# Geogram_ONE.net
KiCad netlist of a schematic drawn in EAGLE
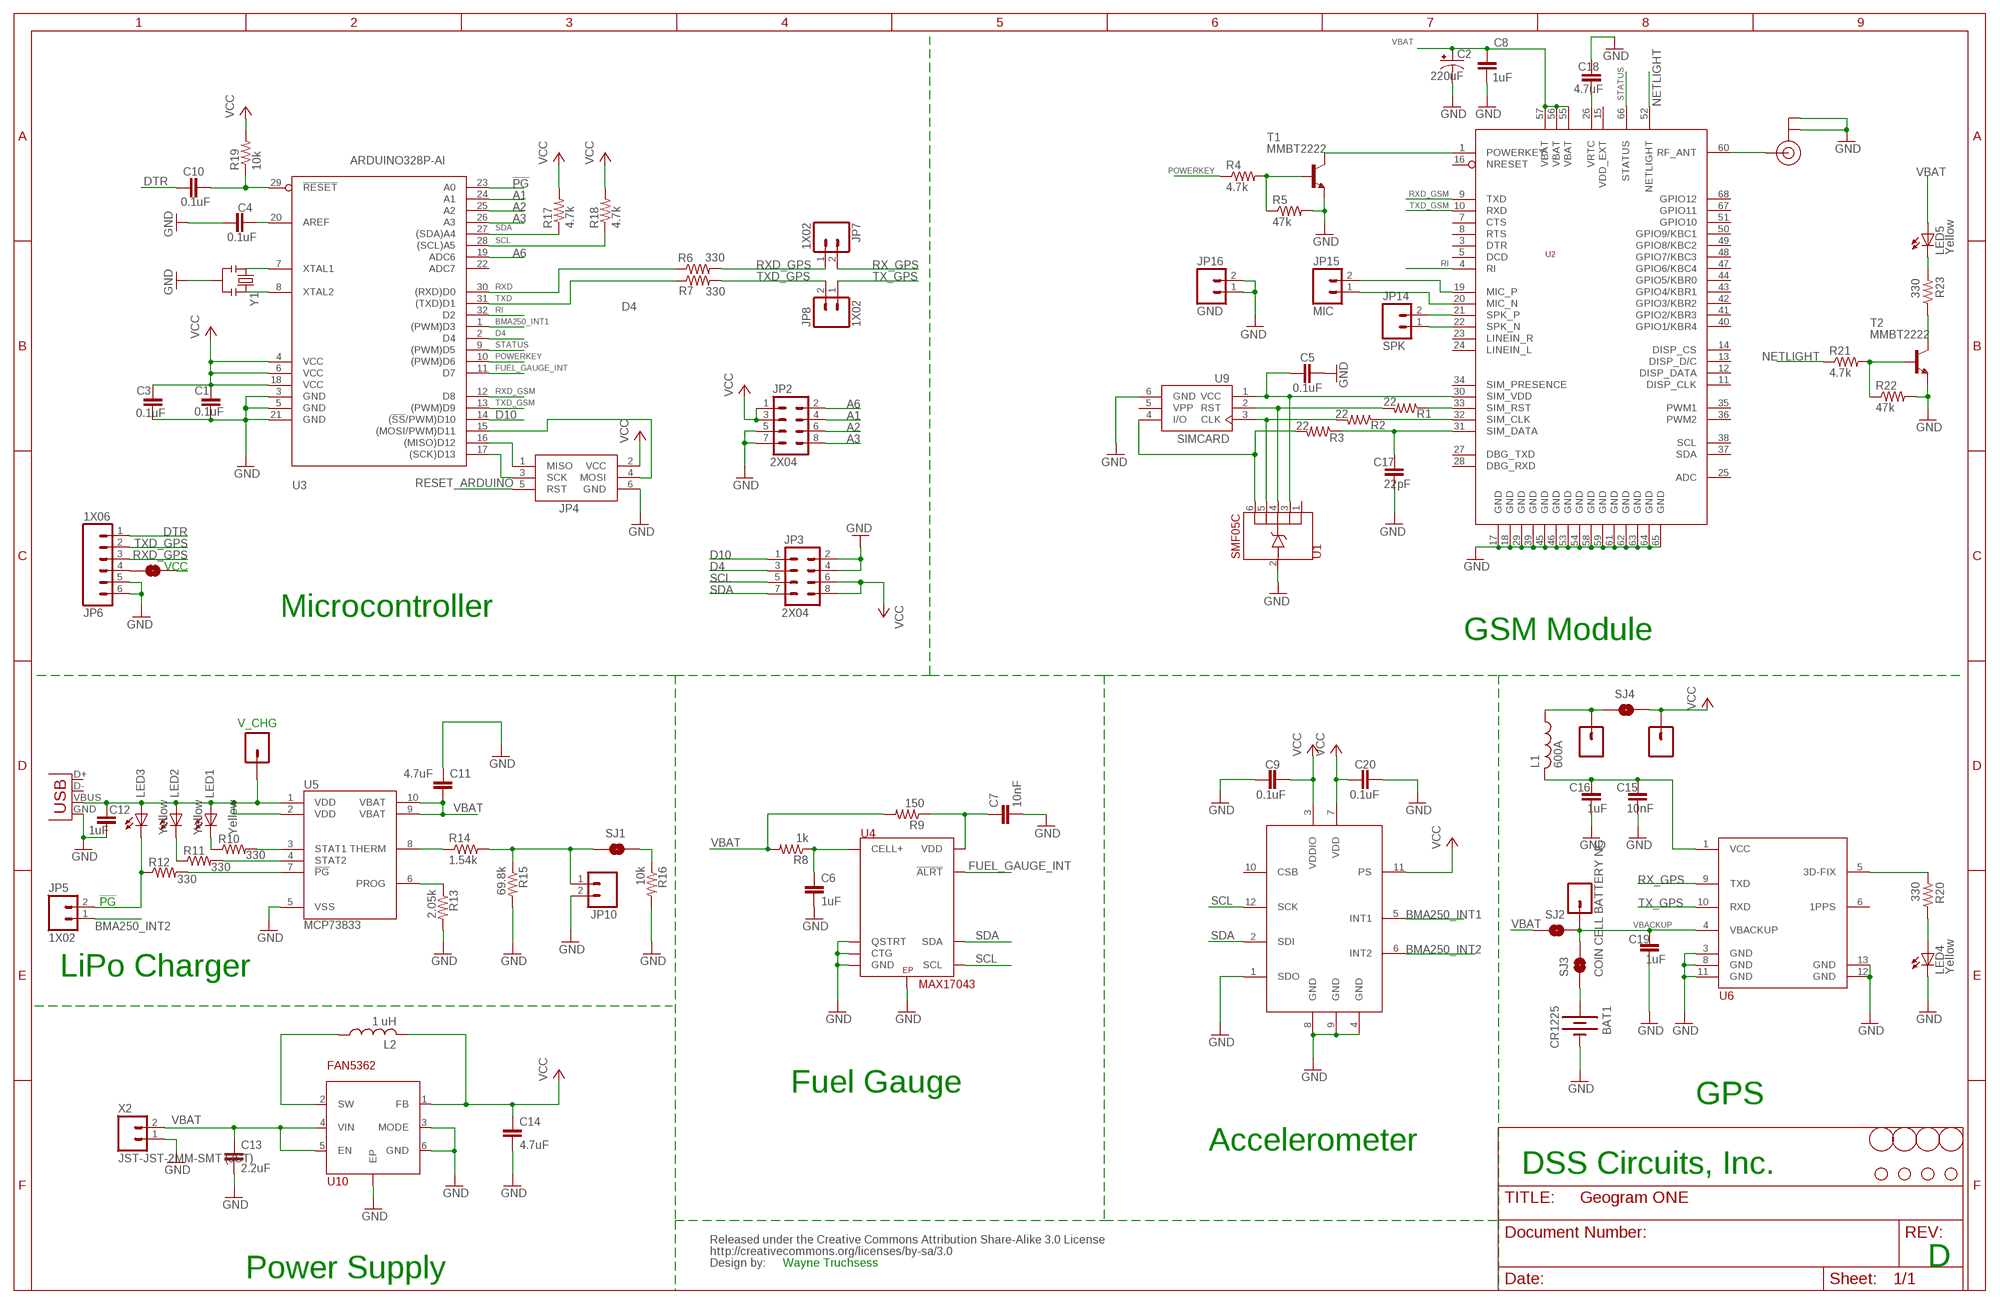
[diagram p0: schematic, sheet 1]

(export (version "E")
  (design (tool "Eeschema 10.0.6"))
  (components
    (comp (ref "BAT1")
      (value "CR1225")
      (footprint "eagle-import:BATTCON_12MM")
      (fields (field (name "MANF") "Keystone Electronics"))
      (libsource (lib "eagle-import") (part "BATTERY12MM"))
    )
    (comp (ref "C1")
      (value "0.1uF")
      (footprint "eagle-import:C0603")
      (fields (field (name "MANF") "Kemet"))
      (libsource (lib "eagle-import") (part "C-EUC0603"))
    )
    (comp (ref "C2")
      (value "220uF")
      (footprint "eagle-import:D_7343-31R")
      (fields (field (name "MANF") "Kemet"))
      (libsource (lib "eagle-import") (part "CPOL-USD/7343-31R"))
    )
    (comp (ref "C3")
      (value "0.1uF")
      (footprint "eagle-import:C0603")
      (fields (field (name "MANF") "Kemet"))
      (libsource (lib "eagle-import") (part "C-EUC0603"))
    )
    (comp (ref "C4")
      (value "0.1uF")
      (footprint "eagle-import:C0603")
      (fields (field (name "MANF") "Kemet"))
      (libsource (lib "eagle-import") (part "C-EUC0603"))
    )
    (comp (ref "C5")
      (value "0.1uF")
      (footprint "eagle-import:C0603")
      (fields (field (name "MANF") "Kemet"))
      (libsource (lib "eagle-import") (part "C-EUC0603"))
    )
    (comp (ref "C6")
      (value "1uF")
      (footprint "eagle-import:C0603")
      (fields (field (name "MANF") "TDK"))
      (libsource (lib "eagle-import") (part "C-EUC0603"))
    )
    (comp (ref "C7")
      (value "10nF")
      (footprint "eagle-import:C0603")
      (fields (field (name "MANF") "Vishay/Vitramon"))
      (libsource (lib "eagle-import") (part "C-EUC0603"))
    )
    (comp (ref "C8")
      (value "1uF")
      (footprint "eagle-import:C0603")
      (fields (field (name "MANF") "TDK"))
      (libsource (lib "eagle-import") (part "C-EUC0603"))
    )
    (comp (ref "C9")
      (value "0.1uF")
      (footprint "eagle-import:C0603")
      (fields (field (name "MANF") "Kemet"))
      (libsource (lib "eagle-import") (part "C-EUC0603"))
    )
    (comp (ref "C10")
      (value "0.1uF")
      (footprint "eagle-import:C0603")
      (fields (field (name "MANF") "Kemet"))
      (libsource (lib "eagle-import") (part "C-EUC0603"))
    )
    (comp (ref "C11")
      (value "4.7uF")
      (footprint "eagle-import:C0603")
      (fields (field (name "MANF") "Kemet"))
      (libsource (lib "eagle-import") (part "C-EUC0603"))
    )
    (comp (ref "C12")
      (value "1uF")
      (footprint "eagle-import:C0603")
      (fields (field (name "MANF") "TDK"))
      (libsource (lib "eagle-import") (part "C-EUC0603"))
    )
    (comp (ref "C13")
      (value "2.2uF")
      (footprint "eagle-import:C0603")
      (fields (field (name "MANF") "Kemet"))
      (libsource (lib "eagle-import") (part "C-EUC0603"))
    )
    (comp (ref "C14")
      (value "4.7uF")
      (footprint "eagle-import:C0603")
      (fields (field (name "MANF") "Kemet"))
      (libsource (lib "eagle-import") (part "C-EUC0603"))
    )
    (comp (ref "C15")
      (value "10nF")
      (footprint "eagle-import:C0603")
      (fields (field (name "MANF") "Vishay/Vitramon"))
      (libsource (lib "eagle-import") (part "C-EUC0603"))
    )
    (comp (ref "C16")
      (value "1uF")
      (footprint "eagle-import:C0603")
      (fields (field (name "MANF") "TDK"))
      (libsource (lib "eagle-import") (part "C-EUC0603"))
    )
    (comp (ref "C17")
      (value "22pF")
      (footprint "eagle-import:C0603")
      (fields (field (name "MANF") "Vishay/Vitramon"))
      (libsource (lib "eagle-import") (part "C-EUC0603"))
    )
    (comp (ref "C18")
      (value "4.7uF")
      (footprint "eagle-import:C0603")
      (fields (field (name "MANF") "Kemet"))
      (libsource (lib "eagle-import") (part "C-EUC0603"))
    )
    (comp (ref "C19")
      (value "1uF")
      (footprint "eagle-import:C0603")
      (fields (field (name "MANF") "TDK"))
      (libsource (lib "eagle-import") (part "C-EUC0603"))
    )
    (comp (ref "C20")
      (value "0.1uF")
      (footprint "eagle-import:C0603")
      (fields (field (name "MANF") "Kemet"))
      (libsource (lib "eagle-import") (part "C-EUC0603"))
    )
    (comp (ref "FIDUCIAL1")
      (value "FIDUCIAL")
      (footprint "eagle-import:FIDUCIAL_1MM")
      (libsource (lib "eagle-import") (part "FIDUCIAL"))
    )
    (comp (ref "FIDUCIAL2")
      (value "FIDUCIAL")
      (footprint "eagle-import:FIDUCIAL_1MM")
      (libsource (lib "eagle-import") (part "FIDUCIAL"))
    )
    (comp (ref "FIDUCIAL3")
      (value "FIDUCIAL")
      (footprint "eagle-import:FIDUCIAL_1MM")
      (libsource (lib "eagle-import") (part "FIDUCIAL"))
    )
    (comp (ref "FIDUCIAL4")
      (value "FIDUCIAL")
      (footprint "eagle-import:FIDUCIAL_1MM")
      (libsource (lib "eagle-import") (part "FIDUCIAL"))
    )
    (comp (ref "JP2")
      (value "2X04")
      (footprint "eagle-import:2X4")
      (fields (field (name "MANF") "4Ucon"))
      (libsource (lib "eagle-import") (part "M04X2"))
    )
    (comp (ref "JP3")
      (value "2X04")
      (footprint "eagle-import:2X4")
      (fields (field (name "MANF") "4Ucon"))
      (libsource (lib "eagle-import") (part "M04X2"))
    )
    (comp (ref "JP4")
      (value "AVRISP-6")
      (footprint "eagle-import:AVRISP")
      (fields (field (name "MANF") "4Ucon"))
      (libsource (lib "eagle-import") (part "AVRISP-6"))
    )
    (comp (ref "JP5")
      (value "1X02")
      (footprint "eagle-import:1X02_NO_SILK")
      (fields (field (name "MANF") "4Ucon"))
      (libsource (lib "eagle-import") (part "M021X02_NO_SILK"))
    )
    (comp (ref "JP6")
      (value "1X06")
      (footprint "eagle-import:1X06")
      (fields (field (name "MANF") "4Ucon"))
      (libsource (lib "eagle-import") (part "M06SIP"))
    )
    (comp (ref "JP7")
      (value "1X02")
      (footprint "eagle-import:1X02_NO_SILK")
      (fields (field (name "MANF") "4Ucon"))
      (libsource (lib "eagle-import") (part "M021X02_NO_SILK"))
    )
    (comp (ref "JP8")
      (value "1X02")
      (footprint "eagle-import:1X02_NO_SILK")
      (fields (field (name "MANF") "4Ucon"))
      (libsource (lib "eagle-import") (part "M021X02_NO_SILK"))
    )
    (comp (ref "JP9")
      (value "V_CHG")
      (footprint "eagle-import:1X01")
      (libsource (lib "eagle-import") (part "M01PTH"))
    )
    (comp (ref "JP10")
      (value "EXT THERMISTER")
      (footprint "eagle-import:1X02_NO_SILK")
      (libsource (lib "eagle-import") (part "M021X02_NO_SILK"))
    )
    (comp (ref "JP11")
      (value "EXT_BAT")
      (footprint "eagle-import:1X01")
      (libsource (lib "eagle-import") (part "M01PTH"))
    )
    (comp (ref "JP12")
      (value "EXT GPS POWER JPR")
      (footprint "eagle-import:1X01")
      (libsource (lib "eagle-import") (part "M01PTH"))
    )
    (comp (ref "JP13")
      (value "EXT GPS POWER JPR")
      (footprint "eagle-import:1X01")
      (libsource (lib "eagle-import") (part "M01PTH"))
    )
    (comp (ref "JP14")
      (value "SPK")
      (footprint "eagle-import:1X02_NO_SILK")
      (libsource (lib "eagle-import") (part "M021X02_NO_SILK"))
    )
    (comp (ref "JP15")
      (value "MIC")
      (footprint "eagle-import:1X02_NO_SILK")
      (libsource (lib "eagle-import") (part "M021X02_NO_SILK"))
    )
    (comp (ref "JP16")
      (value "GND")
      (footprint "eagle-import:1X02_NO_SILK")
      (libsource (lib "eagle-import") (part "M021X02_NO_SILK"))
    )
    (comp (ref "L1")
      (value "600A")
      (footprint "eagle-import:L2012C")
      (fields (field (name "MANF") "TDK"))
      (libsource (lib "eagle-import") (part "L-USL2012C"))
    )
    (comp (ref "L2")
      (value "1 uH")
      (footprint "eagle-import:L2012C")
      (fields (field (name "MANF") "Murata"))
      (libsource (lib "eagle-import") (part "L-USL2012C"))
    )
    (comp (ref "LED1")
      (value "Yellow")
      (footprint "eagle-import:CHIP-LED0603")
      (fields (field (name "MANF") "OSRAM Opto Semiconductors"))
      (libsource (lib "eagle-import") (part "LEDCHIP-LED0603"))
    )
    (comp (ref "LED2")
      (value "Yellow")
      (footprint "eagle-import:CHIP-LED0603")
      (fields (field (name "MANF") "OSRAM Opto Semiconductors"))
      (libsource (lib "eagle-import") (part "LEDCHIP-LED0603"))
    )
    (comp (ref "LED3")
      (value "Yellow")
      (footprint "eagle-import:CHIP-LED0603")
      (fields (field (name "MANF") "OSRAM Opto Semiconductors"))
      (libsource (lib "eagle-import") (part "LEDCHIP-LED0603"))
    )
    (comp (ref "LED4")
      (value "Yellow")
      (footprint "eagle-import:CHIP-LED0603")
      (fields (field (name "MANF") "OSRAM Opto Semiconductors"))
      (libsource (lib "eagle-import") (part "LEDCHIP-LED0603"))
    )
    (comp (ref "LED5")
      (value "Yellow")
      (footprint "eagle-import:CHIP-LED0603")
      (fields (field (name "MANF") "OSRAM Opto Semiconductors"))
      (libsource (lib "eagle-import") (part "LEDCHIP-LED0603"))
    )
    (comp (ref "LICENSE")
      (value "CREATIVE_COMMONS")
      (footprint "eagle-import:CREATIVE_COMMONS")
      (libsource (lib "eagle-import") (part "CREATIVE_COMMONS"))
    )
    (comp (ref "R1")
      (value "22")
      (footprint "eagle-import:R0603")
      (fields (field (name "MANF") "Panasonic Electronic Components"))
      (libsource (lib "eagle-import") (part "R-US_R0603"))
    )
    (comp (ref "R2")
      (value "22")
      (footprint "eagle-import:R0603")
      (fields (field (name "MANF") "Panasonic Electronic Components"))
      (libsource (lib "eagle-import") (part "R-US_R0603"))
    )
    (comp (ref "R3")
      (value "22")
      (footprint "eagle-import:R0603")
      (fields (field (name "MANF") "Panasonic Electronic Components"))
      (libsource (lib "eagle-import") (part "R-US_R0603"))
    )
    (comp (ref "R4")
      (value "4.7k")
      (footprint "eagle-import:R0603")
      (fields (field (name "MANF") "Panasonic Electronic Components"))
      (libsource (lib "eagle-import") (part "R-US_R0603"))
    )
    (comp (ref "R5")
      (value "47k")
      (footprint "eagle-import:R0603")
      (fields (field (name "MANF") "Panasonic Electronic Components"))
      (libsource (lib "eagle-import") (part "R-US_R0603"))
    )
    (comp (ref "R6")
      (value "330")
      (footprint "eagle-import:R0603")
      (fields (field (name "MANF") "Panasonic Electronic Components"))
      (libsource (lib "eagle-import") (part "R-US_R0603"))
    )
    (comp (ref "R7")
      (value "330")
      (footprint "eagle-import:R0603")
      (fields (field (name "MANF") "Panasonic Electronic Components"))
      (libsource (lib "eagle-import") (part "R-US_R0603"))
    )
    (comp (ref "R8")
      (value "1k")
      (footprint "eagle-import:R0603")
      (fields (field (name "MANF") "Panasonic Electronic Components"))
      (libsource (lib "eagle-import") (part "R-US_R0603"))
    )
    (comp (ref "R9")
      (value "150")
      (footprint "eagle-import:R0603")
      (fields (field (name "MANF") "Panasonic Electronic Components"))
      (libsource (lib "eagle-import") (part "R-US_R0603"))
    )
    (comp (ref "R10")
      (value "330")
      (footprint "eagle-import:R0603")
      (fields (field (name "MANF") "Panasonic Electronic Components"))
      (libsource (lib "eagle-import") (part "R-US_R0603"))
    )
    (comp (ref "R11")
      (value "330")
      (footprint "eagle-import:R0603")
      (fields (field (name "MANF") "Panasonic Electronic Components"))
      (libsource (lib "eagle-import") (part "R-US_R0603"))
    )
    (comp (ref "R12")
      (value "330")
      (footprint "eagle-import:R0603")
      (fields (field (name "MANF") "Panasonic Electronic Components"))
      (libsource (lib "eagle-import") (part "R-US_R0603"))
    )
    (comp (ref "R13")
      (value "2.05k")
      (footprint "eagle-import:R0603")
      (fields (field (name "MANF") "Panasonic Electronic Components"))
      (libsource (lib "eagle-import") (part "R-US_R0603"))
    )
    (comp (ref "R14")
      (value "1.54k")
      (footprint "eagle-import:R0603")
      (fields (field (name "MANF") "Vishay/Dale"))
      (libsource (lib "eagle-import") (part "R-US_R0603"))
    )
    (comp (ref "R15")
      (value "69.8k")
      (footprint "eagle-import:R0603")
      (fields (field (name "MANF") "Panasonic Electronic Components"))
      (libsource (lib "eagle-import") (part "R-US_R0603"))
    )
    (comp (ref "R16")
      (value "10k")
      (footprint "eagle-import:R0603")
      (fields (field (name "MANF") "Panasonic Electronic Components"))
      (libsource (lib "eagle-import") (part "R-US_R0603"))
    )
    (comp (ref "R17")
      (value "4.7k")
      (footprint "eagle-import:R0603")
      (fields (field (name "MANF") "Panasonic Electronic Components"))
      (libsource (lib "eagle-import") (part "R-US_R0603"))
    )
    (comp (ref "R18")
      (value "4.7k")
      (footprint "eagle-import:R0603")
      (fields (field (name "MANF") "Panasonic Electronic Components"))
      (libsource (lib "eagle-import") (part "R-US_R0603"))
    )
    (comp (ref "R19")
      (value "10k")
      (footprint "eagle-import:R0603")
      (fields (field (name "MANF") "Panasonic Electronic Components"))
      (libsource (lib "eagle-import") (part "R-US_R0603"))
    )
    (comp (ref "R20")
      (value "330")
      (footprint "eagle-import:R0603")
      (fields (field (name "MANF") "Panasonic Electronic Components"))
      (libsource (lib "eagle-import") (part "R-US_R0603"))
    )
    (comp (ref "R21")
      (value "4.7k")
      (footprint "eagle-import:R0603")
      (fields (field (name "MANF") "Panasonic Electronic Components"))
      (libsource (lib "eagle-import") (part "R-US_R0603"))
    )
    (comp (ref "R22")
      (value "47k")
      (footprint "eagle-import:R0603")
      (fields (field (name "MANF") "Panasonic Electronic Components"))
      (libsource (lib "eagle-import") (part "R-US_R0603"))
    )
    (comp (ref "R23")
      (value "330")
      (footprint "eagle-import:R0603")
      (fields (field (name "MANF") "Panasonic Electronic Components"))
      (libsource (lib "eagle-import") (part "R-US_R0603"))
    )
    (comp (ref "SJ1")
      (value "EXT THERMISTER NC")
      (footprint "eagle-import:SJ_2S-TRACE")
      (libsource (lib "eagle-import") (part "SOLDERJUMPERTRACE"))
    )
    (comp (ref "SJ2")
      (value "LIPO BATTERY NO")
      (footprint "eagle-import:SJ_2S-NO")
      (libsource (lib "eagle-import") (part "SOLDERJUMPERNO"))
    )
    (comp (ref "SJ3")
      (value "COIN CELL BATTERY NC")
      (footprint "eagle-import:SJ_2S-TRACE")
      (libsource (lib "eagle-import") (part "SOLDERJUMPERTRACE"))
    )
    (comp (ref "SJ4")
      (value "EXT GPS POWER NC")
      (footprint "eagle-import:SJ_2S-TRACE")
      (libsource (lib "eagle-import") (part "SOLDERJUMPERTRACE"))
    )
    (comp (ref "SJ5")
      (value "EXT VCC NO")
      (footprint "eagle-import:SJ_2S-NO")
      (libsource (lib "eagle-import") (part "SOLDERJUMPERNO"))
    )
    (comp (ref "STANDOFF1")
      (value "STAND-OFF")
      (footprint "eagle-import:STAND-OFF")
      (libsource (lib "eagle-import") (part "STAND-OFF"))
    )
    (comp (ref "STANDOFF2")
      (value "STAND-OFF")
      (footprint "eagle-import:STAND-OFF")
      (libsource (lib "eagle-import") (part "STAND-OFF"))
    )
    (comp (ref "STANDOFF3")
      (value "STAND-OFF")
      (footprint "eagle-import:STAND-OFF")
      (libsource (lib "eagle-import") (part "STAND-OFF"))
    )
    (comp (ref "STANDOFF4")
      (value "STAND-OFF")
      (footprint "eagle-import:STAND-OFF")
      (libsource (lib "eagle-import") (part "STAND-OFF"))
    )
    (comp (ref "T1")
      (value "MMBT2222")
      (footprint "eagle-import:SOT23-BEC")
      (fields (field (name "MANF") "Fairchild Semiconductor"))
      (libsource (lib "eagle-import") (part "-NPN-SOT23-BECMMBT2222ALT1"))
    )
    (comp (ref "T2")
      (value "MMBT2222")
      (footprint "eagle-import:SOT23-BEC")
      (fields (field (name "MANF") "Fairchild Semiconductor"))
      (libsource (lib "eagle-import") (part "-NPN-SOT23-BECMMBT2222ALT1"))
    )
    (comp (ref "U1")
      (value "SMF05C")
      (footprint "eagle-import:SC70-6L")
      (fields (field (name "MANF") "Semtech"))
      (libsource (lib "eagle-import") (part "SMF05C"))
    )
    (comp (ref "U2")
      (value "SIM900")
      (footprint "eagle-import:SIM900")
      (fields (field (name "MANF") "Simcom"))
      (libsource (lib "eagle-import") (part "SIM900"))
    )
    (comp (ref "U3")
      (value "ARDUINO328P-AI")
      (footprint "eagle-import:TQFP32-08")
      (fields (field (name "MANF") "Atmel"))
      (libsource (lib "eagle-import") (part "ARDUINO328P-AI"))
    )
    (comp (ref "U4")
      (value "MAX17043")
      (footprint "eagle-import:TDFN8")
      (fields (field (name "MANF") "Maxim Integrated Products"))
      (libsource (lib "eagle-import") (part "MAX17043"))
    )
    (comp (ref "U5")
      (value "MCP73833")
      (footprint "eagle-import:MSOP-10")
      (fields (field (name "MANF") "Microchip Technology"))
      (libsource (lib "eagle-import") (part "MCP73833"))
    )
    (comp (ref "U6")
      (value "PA6C")
      (footprint "eagle-import:PA6C")
      (fields (field (name "MANF") "GlobalTop Inc."))
      (libsource (lib "eagle-import") (part "PA6C"))
    )
    (comp (ref "U7")
      (value "BMA250")
      (footprint "eagle-import:12LGA_VGG3-D")
      (fields (field (name "MANF") "Bosch Sensortec"))
      (libsource (lib "eagle-import") (part "BMA250"))
    )
    (comp (ref "U8")
      (value "U.FL")
      (footprint "eagle-import:U.FL")
      (fields (field (name "MANF") "Taoglas"))
      (libsource (lib "eagle-import") (part "U.FL"))
    )
    (comp (ref "U9")
      (value "SIMCARD")
      (footprint "eagle-import:SIMCARD")
      (fields (field (name "MANF") "FCI"))
      (libsource (lib "eagle-import") (part "SIMCARD"))
    )
    (comp (ref "U10")
      (value "FAN5362")
      (footprint "eagle-import:UMLP")
      (fields (field (name "MANF") "Fairchild Semiconductor"))
      (libsource (lib "eagle-import") (part "FAN5362"))
    )
    (comp (ref "X1")
      (value "USBSMD")
      (footprint "eagle-import:USB-MINIB")
      (fields (field (name "MANF") "On Shore Technology Inc"))
      (libsource (lib "eagle-import") (part "USBSMD"))
    )
    (comp (ref "X2")
      (value "JST-JST-2MM-SMT (JST)")
      (footprint "eagle-import:JST")
      (fields (field (name "MANF") "4Ucon"))
      (libsource (lib "eagle-import") (part "JST-JST-2MM-SMT"))
    )
    (comp (ref "Y1")
      (value "8 MHz")
      (footprint "eagle-import:RESONATOR-SMD")
      (fields (field (name "MANF") "Murata"))
      (libsource (lib "eagle-import") (part "RESONATORSMD"))
    )
  )
  (nets
    (net (code "1") (name "/A1") (class "Default")
      (node (ref "JP2") (pin "4") (pinfunction "4_4") (pintype "passive"))
      (node (ref "U3") (pin "24") (pinfunction "A1_24") (pintype "bidirectional"))
    )
    (net (code "2") (name "/A2") (class "Default")
      (node (ref "JP2") (pin "6") (pinfunction "6_6") (pintype "passive"))
      (node (ref "U3") (pin "25") (pinfunction "A2_25") (pintype "bidirectional"))
    )
    (net (code "3") (name "/A3") (class "Default")
      (node (ref "JP2") (pin "8") (pinfunction "8_8") (pintype "passive"))
      (node (ref "U3") (pin "26") (pinfunction "A3_26") (pintype "bidirectional"))
    )
    (net (code "4") (name "/A6") (class "Default")
      (node (ref "JP2") (pin "2") (pinfunction "2_2") (pintype "passive"))
      (node (ref "U3") (pin "19") (pinfunction "ADC6_19") (pintype "bidirectional"))
    )
    (net (code "5") (name "/BMA250_INT1") (class "Default")
      (node (ref "U3") (pin "1") (pinfunction "(PWM)D3_1") (pintype "bidirectional"))
      (node (ref "U7") (pin "5") (pinfunction "INT1_5") (pintype "bidirectional"))
    )
    (net (code "6") (name "/BMA250_INT2") (class "Default")
      (node (ref "JP5") (pin "1") (pinfunction "1_1") (pintype "passive"))
      (node (ref "U7") (pin "6") (pinfunction "INT2_6") (pintype "bidirectional"))
    )
    (net (code "7") (name "/D4") (class "Default")
      (node (ref "JP3") (pin "3") (pinfunction "3_3") (pintype "passive"))
      (node (ref "U3") (pin "2") (pinfunction "D4_2") (pintype "bidirectional"))
    )
    (net (code "8") (name "/D10") (class "Default")
      (node (ref "JP3") (pin "1") (pinfunction "1_1") (pintype "passive"))
      (node (ref "U3") (pin "14") (pinfunction "(~{SS}/PWM)D10_14") (pintype "bidirectional"))
    )
    (net (code "9") (name "/DTR") (class "Default")
      (node (ref "C10") (pin "1") (pinfunction "1_1") (pintype "passive"))
      (node (ref "JP6") (pin "1") (pinfunction "1_1") (pintype "passive"))
    )
    (net (code "10") (name "/FUEL_GAUGE_INT") (class "Default")
      (node (ref "U3") (pin "11") (pinfunction "D7_11") (pintype "bidirectional"))
      (node (ref "U4") (pin "!ALRT") (pinfunction "~{ALRT}_!ALRT") (pintype "bidirectional"))
    )
    (net (code "11") (name "/N$24") (class "Default")
      (node (ref "JP12") (pin "1") (pinfunction "1_1") (pintype "passive"))
      (node (ref "L1") (pin "1") (pinfunction "1_1") (pintype "passive"))
      (node (ref "SJ4") (pin "1") (pinfunction "1_1") (pintype "passive"))
      (node (ref "SJ5") (pin "1") (pinfunction "1_1") (pintype "passive"))
    )
    (net (code "12") (name "/NETLIGHT") (class "Default")
      (node (ref "R21") (pin "1") (pinfunction "1_1") (pintype "passive"))
      (node (ref "U2") (pin "52") (pinfunction "NETLIGHT_52") (pintype "bidirectional"))
    )
    (net (code "13") (name "/POWERKEY") (class "Default")
      (node (ref "R4") (pin "1") (pinfunction "1_1") (pintype "passive"))
      (node (ref "U3") (pin "10") (pinfunction "(PWM)D6_10") (pintype "bidirectional"))
    )
    (net (code "14") (name "/RESET_ARDUINO") (class "Default")
      (node (ref "C10") (pin "2") (pinfunction "2_2") (pintype "passive"))
      (node (ref "JP4") (pin "5") (pinfunction "RST_5") (pintype "output"))
      (node (ref "R19") (pin "1") (pinfunction "1_1") (pintype "passive"))
      (node (ref "U3") (pin "29") (pinfunction "~{RESET}_29") (pintype "input"))
    )
    (net (code "15") (name "/RI") (class "Default")
      (node (ref "U2") (pin "4") (pinfunction "RI_4") (pintype "bidirectional"))
      (node (ref "U3") (pin "32") (pinfunction "D2_32") (pintype "bidirectional"))
    )
    (net (code "16") (name "/RXD") (class "Default")
      (node (ref "R6") (pin "1") (pinfunction "1_1") (pintype "passive"))
      (node (ref "U3") (pin "30") (pinfunction "(RXD)D0_30") (pintype "bidirectional"))
    )
    (net (code "17") (name "/RXD_GPS") (class "Default")
      (node (ref "JP6") (pin "3") (pinfunction "3_3") (pintype "passive"))
      (node (ref "JP7") (pin "1") (pinfunction "1_1") (pintype "passive"))
      (node (ref "R6") (pin "2") (pinfunction "2_2") (pintype "passive"))
    )
    (net (code "18") (name "/RXD_GSM") (class "Default")
      (node (ref "U2") (pin "9") (pinfunction "TXD_9") (pintype "bidirectional"))
      (node (ref "U3") (pin "12") (pinfunction "D8_12") (pintype "bidirectional"))
    )
    (net (code "19") (name "/RX_GPS") (class "Default")
      (node (ref "JP7") (pin "2") (pinfunction "2_2") (pintype "passive"))
      (node (ref "U6") (pin "9") (pinfunction "TXD_9") (pintype "output"))
    )
    (net (code "20") (name "/SCL") (class "Default")
      (node (ref "JP3") (pin "5") (pinfunction "5_5") (pintype "passive"))
      (node (ref "R18") (pin "1") (pinfunction "1_1") (pintype "passive"))
      (node (ref "U3") (pin "28") (pinfunction "(SCL)A5_28") (pintype "bidirectional"))
      (node (ref "U4") (pin "SCL") (pinfunction "SCL_SCL") (pintype "bidirectional"))
      (node (ref "U7") (pin "12") (pinfunction "SCK_12") (pintype "bidirectional"))
    )
    (net (code "21") (name "/SDA") (class "Default")
      (node (ref "JP3") (pin "7") (pinfunction "7_7") (pintype "passive"))
      (node (ref "R17") (pin "1") (pinfunction "1_1") (pintype "passive"))
      (node (ref "U3") (pin "27") (pinfunction "(SDA)A4_27") (pintype "bidirectional"))
      (node (ref "U4") (pin "SDA") (pinfunction "SDA_SDA") (pintype "bidirectional"))
      (node (ref "U7") (pin "2") (pinfunction "SDI_2") (pintype "bidirectional"))
    )
    (net (code "22") (name "/STATUS") (class "Default")
      (node (ref "U2") (pin "66") (pinfunction "STATUS_66") (pintype "bidirectional"))
      (node (ref "U3") (pin "9") (pinfunction "(PWM)D5_9") (pintype "bidirectional"))
    )
    (net (code "23") (name "/TXD") (class "Default")
      (node (ref "R7") (pin "1") (pinfunction "1_1") (pintype "passive"))
      (node (ref "U3") (pin "31") (pinfunction "(TXD)D1_31") (pintype "bidirectional"))
    )
    (net (code "24") (name "/TXD_GPS") (class "Default")
      (node (ref "JP6") (pin "2") (pinfunction "2_2") (pintype "passive"))
      (node (ref "JP8") (pin "2") (pinfunction "2_2") (pintype "passive"))
      (node (ref "R7") (pin "2") (pinfunction "2_2") (pintype "passive"))
    )
    (net (code "25") (name "/TXD_GSM") (class "Default")
      (node (ref "U2") (pin "10") (pinfunction "RXD_10") (pintype "bidirectional"))
      (node (ref "U3") (pin "13") (pinfunction "(PWM)D9_13") (pintype "bidirectional"))
    )
    (net (code "26") (name "/TX_GPS") (class "Default")
      (node (ref "JP8") (pin "1") (pinfunction "1_1") (pintype "passive"))
      (node (ref "U6") (pin "10") (pinfunction "RXD_10") (pintype "input"))
    )
    (net (code "27") (name "/VBACKUP") (class "Default")
      (node (ref "C19") (pin "2") (pinfunction "2_2") (pintype "passive"))
      (node (ref "JP11") (pin "1") (pinfunction "1_1") (pintype "passive"))
      (node (ref "SJ2") (pin "2") (pinfunction "2_2") (pintype "passive"))
      (node (ref "SJ3") (pin "2") (pinfunction "2_2") (pintype "passive"))
      (node (ref "U6") (pin "4") (pinfunction "VBACKUP_4") (pintype "power_in"))
    )
    (net (code "28") (name "/VBAT") (class "Default")
      (node (ref "C11") (pin "2") (pinfunction "2_2") (pintype "passive"))
      (node (ref "C13") (pin "1") (pinfunction "1_1") (pintype "passive"))
      (node (ref "C2") (pin "+") (pinfunction "+_+") (pintype "passive"))
      (node (ref "C8") (pin "1") (pinfunction "1_1") (pintype "passive"))
      (node (ref "LED5") (pin "A") (pinfunction "A_A") (pintype "passive"))
      (node (ref "R8") (pin "2") (pinfunction "2_2") (pintype "passive"))
      (node (ref "R9") (pin "2") (pinfunction "2_2") (pintype "passive"))
      (node (ref "SJ2") (pin "1") (pinfunction "1_1") (pintype "passive"))
      (node (ref "U10") (pin "4") (pinfunction "VIN_4") (pintype "power_in"))
      (node (ref "U10") (pin "5") (pinfunction "EN_5") (pintype "bidirectional"))
      (node (ref "U2") (pin "55") (pinfunction "VBAT_55") (pintype "power_in"))
      (node (ref "U2") (pin "56") (pinfunction "VBAT_56") (pintype "power_in"))
      (node (ref "U2") (pin "57") (pinfunction "VBAT_57") (pintype "power_in"))
      (node (ref "U5") (pin "10") (pinfunction "VBAT_10") (pintype "bidirectional"))
      (node (ref "U5") (pin "9") (pinfunction "VBAT_9") (pintype "bidirectional"))
      (node (ref "X2") (pin "2") (pinfunction "2_2") (pintype "passive"))
    )
    (net (code "29") (name "/VDD_EXT") (class "Default")
      (node (ref "U2") (pin "15") (pinfunction "VDD_EXT_15") (pintype "power_in"))
    )
    (net (code "30") (name "/VPP") (class "Default")
      (node (ref "U9") (pin "5") (pinfunction "VPP_5") (pintype "power_in"))
    )
    (net (code "31") (name "/~{PG}") (class "Default")
      (node (ref "JP5") (pin "2") (pinfunction "2_2") (pintype "passive"))
      (node (ref "LED3") (pin "C") (pinfunction "C_C") (pintype "passive"))
      (node (ref "R12") (pin "1") (pinfunction "1_1") (pintype "passive"))
      (node (ref "U3") (pin "23") (pinfunction "A0_23") (pintype "bidirectional"))
    )
    (net (code "32") (name "GND") (class "Default")
      (node (ref "BAT1") (pin "GND") (pinfunction "-_GND") (pintype "power_in"))
      (node (ref "C1") (pin "2") (pinfunction "2_2") (pintype "passive"))
      (node (ref "C11") (pin "1") (pinfunction "1_1") (pintype "passive"))
      (node (ref "C12") (pin "2") (pinfunction "2_2") (pintype "passive"))
      (node (ref "C13") (pin "2") (pinfunction "2_2") (pintype "passive"))
      (node (ref "C14") (pin "2") (pinfunction "2_2") (pintype "passive"))
      (node (ref "C15") (pin "1") (pinfunction "1_1") (pintype "passive"))
      (node (ref "C16") (pin "1") (pinfunction "1_1") (pintype "passive"))
      (node (ref "C17") (pin "1") (pinfunction "1_1") (pintype "passive"))
      (node (ref "C18") (pin "1") (pinfunction "1_1") (pintype "passive"))
      (node (ref "C19") (pin "1") (pinfunction "1_1") (pintype "passive"))
      (node (ref "C2") (pin "-") (pinfunction "-_-") (pintype "passive"))
      (node (ref "C20") (pin "1") (pinfunction "1_1") (pintype "passive"))
      (node (ref "C3") (pin "2") (pinfunction "2_2") (pintype "passive"))
      (node (ref "C4") (pin "1") (pinfunction "1_1") (pintype "passive"))
      (node (ref "C5") (pin "2") (pinfunction "2_2") (pintype "passive"))
      (node (ref "C6") (pin "2") (pinfunction "2_2") (pintype "passive"))
      (node (ref "C7") (pin "2") (pinfunction "2_2") (pintype "passive"))
      (node (ref "C8") (pin "2") (pinfunction "2_2") (pintype "passive"))
      (node (ref "C9") (pin "2") (pinfunction "2_2") (pintype "passive"))
      (node (ref "JP10") (pin "2") (pinfunction "2_2") (pintype "passive"))
      (node (ref "JP16") (pin "1") (pinfunction "1_1") (pintype "passive"))
      (node (ref "JP16") (pin "2") (pinfunction "2_2") (pintype "passive"))
      (node (ref "JP2") (pin "5") (pinfunction "5_5") (pintype "passive"))
      (node (ref "JP2") (pin "7") (pinfunction "7_7") (pintype "passive"))
      (node (ref "JP3") (pin "2") (pinfunction "2_2") (pintype "passive"))
      (node (ref "JP3") (pin "4") (pinfunction "4_4") (pintype "passive"))
      (node (ref "JP4") (pin "6") (pinfunction "GND_6") (pintype "power_in"))
      (node (ref "JP6") (pin "5") (pinfunction "5_5") (pintype "passive"))
      (node (ref "JP6") (pin "6") (pinfunction "6_6") (pintype "passive"))
      (node (ref "LED4") (pin "C") (pinfunction "C_C") (pintype "passive"))
      (node (ref "R13") (pin "2") (pinfunction "2_2") (pintype "passive"))
      (node (ref "R15") (pin "2") (pinfunction "2_2") (pintype "passive"))
      (node (ref "R16") (pin "2") (pinfunction "2_2") (pintype "passive"))
      (node (ref "R22") (pin "2") (pinfunction "2_2") (pintype "passive"))
      (node (ref "R5") (pin "2") (pinfunction "2_2") (pintype "passive"))
      (node (ref "T1") (pin "E") (pinfunction "E_E") (pintype "passive"))
      (node (ref "T2") (pin "E") (pinfunction "E_E") (pintype "passive"))
      (node (ref "U1") (pin "2") (pinfunction "2_2") (pintype "power_in"))
      (node (ref "U10") (pin "3") (pinfunction "MODE_3") (pintype "bidirectional"))
      (node (ref "U10") (pin "6") (pinfunction "GND_6") (pintype "power_in"))
      (node (ref "U10") (pin "7") (pinfunction "EP_7") (pintype "power_in"))
      (node (ref "U2") (pin "17") (pinfunction "GND_17") (pintype "power_in"))
      (node (ref "U2") (pin "18") (pinfunction "GND_18") (pintype "power_in"))
      (node (ref "U2") (pin "29") (pinfunction "GND_29") (pintype "power_in"))
      (node (ref "U2") (pin "39") (pinfunction "GND_39") (pintype "power_in"))
      (node (ref "U2") (pin "45") (pinfunction "GND_45") (pintype "power_in"))
      (node (ref "U2") (pin "46") (pinfunction "GND_46") (pintype "power_in"))
      (node (ref "U2") (pin "53") (pinfunction "GND_53") (pintype "power_in"))
      (node (ref "U2") (pin "54") (pinfunction "GND_54") (pintype "power_in"))
      (node (ref "U2") (pin "58") (pinfunction "GND_58") (pintype "power_in"))
      (node (ref "U2") (pin "59") (pinfunction "GND_59") (pintype "power_in"))
      (node (ref "U2") (pin "61") (pinfunction "GND_61") (pintype "power_in"))
      (node (ref "U2") (pin "62") (pinfunction "GND_62") (pintype "power_in"))
      (node (ref "U2") (pin "63") (pinfunction "GND_63") (pintype "power_in"))
      (node (ref "U2") (pin "64") (pinfunction "GND_64") (pintype "power_in"))
      (node (ref "U2") (pin "65") (pinfunction "GND_65") (pintype "power_in"))
      (node (ref "U3") (pin "21") (pinfunction "GND_21") (pintype "power_in"))
      (node (ref "U3") (pin "3") (pinfunction "GND_3") (pintype "power_in"))
      (node (ref "U3") (pin "5") (pinfunction "GND_5") (pintype "power_in"))
      (node (ref "U4") (pin "CTG") (pinfunction "CTG_CTG") (pintype "bidirectional"))
      (node (ref "U4") (pin "EP") (pinfunction "EP_EP") (pintype "power_in"))
      (node (ref "U4") (pin "GND") (pinfunction "GND_GND") (pintype "power_in"))
      (node (ref "U4") (pin "QSTRT") (pinfunction "QSTRT_QSTRT") (pintype "bidirectional"))
      (node (ref "U5") (pin "5") (pinfunction "VSS_5") (pintype "bidirectional"))
      (node (ref "U6") (pin "11") (pinfunction "GND_11") (pintype "power_in"))
      (node (ref "U6") (pin "12") (pinfunction "GND_12") (pintype "power_in"))
      (node (ref "U6") (pin "13") (pinfunction "GND_13") (pintype "power_in"))
      (node (ref "U6") (pin "3") (pinfunction "GND_3") (pintype "power_in"))
      (node (ref "U6") (pin "8") (pinfunction "GND_8") (pintype "power_in"))
      (node (ref "U7") (pin "1") (pinfunction "SDO_1") (pintype "bidirectional"))
      (node (ref "U7") (pin "4") (pinfunction "GND_4") (pintype "bidirectional"))
      (node (ref "U7") (pin "8") (pinfunction "GND_8") (pintype "bidirectional"))
      (node (ref "U7") (pin "9") (pinfunction "GND_9") (pintype "bidirectional"))
      (node (ref "U8") (pin "P$1") (pinfunction "GND_P$1") (pintype "bidirectional"))
      (node (ref "U8") (pin "P$2") (pinfunction "GND_P$2") (pintype "bidirectional"))
      (node (ref "U9") (pin "6") (pinfunction "GND_6") (pintype "power_in"))
      (node (ref "X1") (pin "GND") (pinfunction "GND_GND") (pintype "bidirectional"))
      (node (ref "X2") (pin "1") (pinfunction "1_1") (pintype "passive"))
      (node (ref "Y1") (pin "2") (pinfunction "2_2") (pintype "passive"))
    )
    (net (code "33") (name "Net-(BAT1-+)") (class "Default")
      (node (ref "BAT1") (pin "PWR@2") (pinfunction "+_PWR@2") (pintype "power_in"))
      (node (ref "SJ3") (pin "1") (pinfunction "1_1") (pintype "passive"))
    )
    (net (code "34") (name "Net-(C6-Pad1)") (class "Default")
      (node (ref "C6") (pin "1") (pinfunction "1_1") (pintype "passive"))
      (node (ref "R8") (pin "1") (pinfunction "1_1") (pintype "passive"))
      (node (ref "U4") (pin "CELL+") (pinfunction "CELL+_CELL+") (pintype "power_in"))
    )
    (net (code "35") (name "Net-(C7-Pad1)") (class "Default")
      (node (ref "C7") (pin "1") (pinfunction "1_1") (pintype "passive"))
      (node (ref "R9") (pin "1") (pinfunction "1_1") (pintype "passive"))
      (node (ref "U4") (pin "VDD") (pinfunction "VDD_VDD") (pintype "power_in"))
    )
    (net (code "36") (name "Net-(C12-Pad1)") (class "Default")
      (node (ref "C12") (pin "1") (pinfunction "1_1") (pintype "passive"))
      (node (ref "JP9") (pin "1") (pinfunction "1_1") (pintype "passive"))
      (node (ref "LED1") (pin "A") (pinfunction "A_A") (pintype "passive"))
      (node (ref "LED2") (pin "A") (pinfunction "A_A") (pintype "passive"))
      (node (ref "LED3") (pin "A") (pinfunction "A_A") (pintype "passive"))
      (node (ref "U5") (pin "1") (pinfunction "VDD_1") (pintype "bidirectional"))
      (node (ref "U5") (pin "2") (pinfunction "VDD_2") (pintype "bidirectional"))
      (node (ref "X1") (pin "VBUS") (pinfunction "VBUS_VBUS") (pintype "bidirectional"))
    )
    (net (code "37") (name "Net-(JP4-MISO)") (class "Default")
      (node (ref "JP4") (pin "1") (pinfunction "MISO_1") (pintype "input"))
      (node (ref "U3") (pin "16") (pinfunction "(MISO)D12_16") (pintype "bidirectional"))
    )
    (net (code "38") (name "Net-(JP4-MOSI)") (class "Default")
      (node (ref "JP4") (pin "4") (pinfunction "MOSI_4") (pintype "output"))
      (node (ref "U3") (pin "15") (pinfunction "(MOSI/PWM)D11_15") (pintype "bidirectional"))
    )
    (net (code "39") (name "Net-(JP4-SCK)") (class "Default")
      (node (ref "JP4") (pin "3") (pinfunction "SCK_3") (pintype "output"))
      (node (ref "U3") (pin "17") (pinfunction "(SCK)D13_17") (pintype "bidirectional"))
    )
    (net (code "40") (name "Net-(JP6-Pad4)") (class "Default")
      (node (ref "JP6") (pin "4") (pinfunction "4_4") (pintype "passive"))
      (node (ref "SJ5") (pin "2") (pinfunction "2_2") (pintype "passive"))
    )
    (net (code "41") (name "Net-(JP10-Pad1)") (class "Default")
      (node (ref "JP10") (pin "1") (pinfunction "1_1") (pintype "passive"))
      (node (ref "R14") (pin "2") (pinfunction "2_2") (pintype "passive"))
      (node (ref "R15") (pin "1") (pinfunction "1_1") (pintype "passive"))
      (node (ref "SJ1") (pin "1") (pinfunction "1_1") (pintype "passive"))
    )
    (net (code "42") (name "Net-(LED1-PadC)") (class "Default")
      (node (ref "LED1") (pin "C") (pinfunction "C_C") (pintype "passive"))
      (node (ref "R10") (pin "1") (pinfunction "1_1") (pintype "passive"))
    )
    (net (code "43") (name "Net-(LED2-PadC)") (class "Default")
      (node (ref "LED2") (pin "C") (pinfunction "C_C") (pintype "passive"))
      (node (ref "R11") (pin "1") (pinfunction "1_1") (pintype "passive"))
    )
    (net (code "44") (name "Net-(LED4-PadA)") (class "Default")
      (node (ref "LED4") (pin "A") (pinfunction "A_A") (pintype "passive"))
      (node (ref "R20") (pin "1") (pinfunction "1_1") (pintype "passive"))
    )
    (net (code "45") (name "Net-(LED5-PadC)") (class "Default")
      (node (ref "LED5") (pin "C") (pinfunction "C_C") (pintype "passive"))
      (node (ref "R23") (pin "2") (pinfunction "2_2") (pintype "passive"))
    )
    (net (code "46") (name "Net-(R4-Pad2)") (class "Default")
      (node (ref "R4") (pin "2") (pinfunction "2_2") (pintype "passive"))
      (node (ref "R5") (pin "1") (pinfunction "1_1") (pintype "passive"))
      (node (ref "T1") (pin "B") (pinfunction "B_B") (pintype "passive"))
    )
    (net (code "47") (name "Net-(R16-Pad1)") (class "Default")
      (node (ref "R16") (pin "1") (pinfunction "1_1") (pintype "passive"))
      (node (ref "SJ1") (pin "2") (pinfunction "2_2") (pintype "passive"))
    )
    (net (code "48") (name "Net-(R21-Pad2)") (class "Default")
      (node (ref "R21") (pin "2") (pinfunction "2_2") (pintype "passive"))
      (node (ref "R22") (pin "1") (pinfunction "1_1") (pintype "passive"))
      (node (ref "T2") (pin "B") (pinfunction "B_B") (pintype "passive"))
    )
    (net (code "49") (name "Net-(R23-Pad1)") (class "Default")
      (node (ref "R23") (pin "1") (pinfunction "1_1") (pintype "passive"))
      (node (ref "T2") (pin "C") (pinfunction "C_C") (pintype "passive"))
    )
    (net (code "50") (name "Net-(U2-MIC_N)") (class "Default")
      (node (ref "JP15") (pin "1") (pinfunction "1_1") (pintype "passive"))
      (node (ref "U2") (pin "20") (pinfunction "MIC_N_20") (pintype "bidirectional"))
    )
    (net (code "51") (name "Net-(U2-MIC_P)") (class "Default")
      (node (ref "JP15") (pin "2") (pinfunction "2_2") (pintype "passive"))
      (node (ref "U2") (pin "19") (pinfunction "MIC_P_19") (pintype "bidirectional"))
    )
    (net (code "52") (name "Net-(U2-POWERKEY)") (class "Default")
      (node (ref "T1") (pin "C") (pinfunction "C_C") (pintype "passive"))
      (node (ref "U2") (pin "1") (pinfunction "POWERKEY_1") (pintype "input"))
    )
    (net (code "53") (name "Net-(U2-RF_ANT)") (class "Default")
      (node (ref "U2") (pin "60") (pinfunction "RF_ANT_60") (pintype "bidirectional"))
      (node (ref "U8") (pin "P$3") (pinfunction "SIGNAL_P$3") (pintype "bidirectional"))
    )
    (net (code "54") (name "Net-(U2-SIM_CLK)") (class "Default")
      (node (ref "R2") (pin "1") (pinfunction "1_1") (pintype "passive"))
      (node (ref "U2") (pin "32") (pinfunction "SIM_CLK_32") (pintype "bidirectional"))
    )
    (net (code "55") (name "Net-(U2-SIM_DATA)") (class "Default")
      (node (ref "C17") (pin "2") (pinfunction "2_2") (pintype "passive"))
      (node (ref "R3") (pin "1") (pinfunction "1_1") (pintype "passive"))
      (node (ref "U2") (pin "31") (pinfunction "SIM_DATA_31") (pintype "bidirectional"))
    )
    (net (code "56") (name "Net-(U2-SIM_RST)") (class "Default")
      (node (ref "R1") (pin "1") (pinfunction "1_1") (pintype "passive"))
      (node (ref "U2") (pin "33") (pinfunction "SIM_RST_33") (pintype "bidirectional"))
    )
    (net (code "57") (name "Net-(U2-SIM_VDD)") (class "Default")
      (node (ref "C5") (pin "1") (pinfunction "1_1") (pintype "passive"))
      (node (ref "U1") (pin "3") (pinfunction "3_3") (pintype "bidirectional"))
      (node (ref "U2") (pin "30") (pinfunction "SIM_VDD_30") (pintype "bidirectional"))
      (node (ref "U9") (pin "1") (pinfunction "VCC_1") (pintype "power_in"))
    )
    (net (code "58") (name "Net-(U2-SPK_N)") (class "Default")
      (node (ref "JP14") (pin "1") (pinfunction "1_1") (pintype "passive"))
      (node (ref "U2") (pin "22") (pinfunction "SPK_N_22") (pintype "bidirectional"))
    )
    (net (code "59") (name "Net-(U2-SPK_P)") (class "Default")
      (node (ref "JP14") (pin "2") (pinfunction "2_2") (pintype "passive"))
      (node (ref "U2") (pin "21") (pinfunction "SPK_P_21") (pintype "bidirectional"))
    )
    (net (code "60") (name "Net-(U2-VRTC)") (class "Default")
      (node (ref "C18") (pin "2") (pinfunction "2_2") (pintype "passive"))
      (node (ref "U2") (pin "26") (pinfunction "VRTC_26") (pintype "bidirectional"))
    )
    (net (code "61") (name "Net-(U3-AREF)") (class "Default")
      (node (ref "C4") (pin "2") (pinfunction "2_2") (pintype "passive"))
      (node (ref "U3") (pin "20") (pinfunction "AREF_20") (pintype "bidirectional"))
    )
    (net (code "62") (name "Net-(U3-XTAL1)") (class "Default")
      (node (ref "U3") (pin "7") (pinfunction "XTAL1_7") (pintype "bidirectional"))
      (node (ref "Y1") (pin "1") (pinfunction "1_1") (pintype "passive"))
    )
    (net (code "63") (name "Net-(U3-XTAL2)") (class "Default")
      (node (ref "U3") (pin "8") (pinfunction "XTAL2_8") (pintype "bidirectional"))
      (node (ref "Y1") (pin "3") (pinfunction "3_3") (pintype "passive"))
    )
    (net (code "64") (name "Net-(U5-PROG)") (class "Default")
      (node (ref "R13") (pin "1") (pinfunction "1_1") (pintype "passive"))
      (node (ref "U5") (pin "6") (pinfunction "PROG_6") (pintype "bidirectional"))
    )
    (net (code "65") (name "Net-(U5-STAT1)") (class "Default")
      (node (ref "R10") (pin "2") (pinfunction "2_2") (pintype "passive"))
      (node (ref "U5") (pin "3") (pinfunction "STAT1_3") (pintype "bidirectional"))
    )
    (net (code "66") (name "Net-(U5-STAT2)") (class "Default")
      (node (ref "R11") (pin "2") (pinfunction "2_2") (pintype "passive"))
      (node (ref "U5") (pin "4") (pinfunction "STAT2_4") (pintype "bidirectional"))
    )
    (net (code "67") (name "Net-(U5-THERM)") (class "Default")
      (node (ref "R14") (pin "1") (pinfunction "1_1") (pintype "passive"))
      (node (ref "U5") (pin "8") (pinfunction "THERM_8") (pintype "bidirectional"))
    )
    (net (code "68") (name "Net-(U5-~{PG})") (class "Default")
      (node (ref "R12") (pin "2") (pinfunction "2_2") (pintype "passive"))
      (node (ref "U5") (pin "7") (pinfunction "~{PG}_7") (pintype "bidirectional"))
    )
    (net (code "69") (name "Net-(U6-3D-FIX)") (class "Default")
      (node (ref "R20") (pin "2") (pinfunction "2_2") (pintype "passive"))
      (node (ref "U6") (pin "5") (pinfunction "3D-FIX_5") (pintype "output"))
    )
    (net (code "70") (name "Net-(U6-VCC)") (class "Default")
      (node (ref "C15") (pin "2") (pinfunction "2_2") (pintype "passive"))
      (node (ref "C16") (pin "2") (pinfunction "2_2") (pintype "passive"))
      (node (ref "L1") (pin "2") (pinfunction "2_2") (pintype "passive"))
      (node (ref "U6") (pin "1") (pinfunction "VCC_1") (pintype "power_in"))
    )
    (net (code "71") (name "Net-(U9-CLK)") (class "Default")
      (node (ref "R2") (pin "2") (pinfunction "2_2") (pintype "passive"))
      (node (ref "U1") (pin "5") (pinfunction "5_5") (pintype "bidirectional"))
      (node (ref "U9") (pin "3") (pinfunction "CLK_3") (pintype "input"))
    )
    (net (code "72") (name "Net-(U9-I{slash}O)") (class "Default")
      (node (ref "R3") (pin "2") (pinfunction "2_2") (pintype "passive"))
      (node (ref "U1") (pin "6") (pinfunction "6_6") (pintype "bidirectional"))
      (node (ref "U9") (pin "4") (pinfunction "I/O_4") (pintype "bidirectional"))
    )
    (net (code "73") (name "Net-(U9-RST)") (class "Default")
      (node (ref "R1") (pin "2") (pinfunction "2_2") (pintype "passive"))
      (node (ref "U1") (pin "4") (pinfunction "4_4") (pintype "bidirectional"))
      (node (ref "U9") (pin "2") (pinfunction "RST_2") (pintype "input"))
    )
    (net (code "74") (name "Net-(U10-SW)") (class "Default")
      (node (ref "L2") (pin "1") (pinfunction "1_1") (pintype "passive"))
      (node (ref "U10") (pin "2") (pinfunction "SW_2") (pintype "bidirectional"))
    )
    (net (code "75") (name "VCC") (class "Default")
      (node (ref "C1") (pin "1") (pinfunction "1_1") (pintype "passive"))
      (node (ref "C14") (pin "1") (pinfunction "1_1") (pintype "passive"))
      (node (ref "C20") (pin "2") (pinfunction "2_2") (pintype "passive"))
      (node (ref "C3") (pin "1") (pinfunction "1_1") (pintype "passive"))
      (node (ref "C9") (pin "1") (pinfunction "1_1") (pintype "passive"))
      (node (ref "JP13") (pin "1") (pinfunction "1_1") (pintype "passive"))
      (node (ref "JP2") (pin "1") (pinfunction "1_1") (pintype "passive"))
      (node (ref "JP2") (pin "3") (pinfunction "3_3") (pintype "passive"))
      (node (ref "JP3") (pin "6") (pinfunction "6_6") (pintype "passive"))
      (node (ref "JP3") (pin "8") (pinfunction "8_8") (pintype "passive"))
      (node (ref "JP4") (pin "2") (pinfunction "VCC_2") (pintype "power_in"))
      (node (ref "L2") (pin "2") (pinfunction "2_2") (pintype "passive"))
      (node (ref "R17") (pin "2") (pinfunction "2_2") (pintype "passive"))
      (node (ref "R18") (pin "2") (pinfunction "2_2") (pintype "passive"))
      (node (ref "R19") (pin "2") (pinfunction "2_2") (pintype "passive"))
      (node (ref "SJ4") (pin "2") (pinfunction "2_2") (pintype "passive"))
      (node (ref "U10") (pin "1") (pinfunction "FB_1") (pintype "bidirectional"))
      (node (ref "U3") (pin "18") (pinfunction "VCC_18") (pintype "power_in"))
      (node (ref "U3") (pin "4") (pinfunction "VCC_4") (pintype "power_in"))
      (node (ref "U3") (pin "6") (pinfunction "VCC_6") (pintype "power_in"))
      (node (ref "U7") (pin "11") (pinfunction "PS_11") (pintype "bidirectional"))
      (node (ref "U7") (pin "3") (pinfunction "VDDIO_3") (pintype "bidirectional"))
      (node (ref "U7") (pin "7") (pinfunction "VDD_7") (pintype "bidirectional"))
    )
    (net (code "76") (name "unconnected-(U1-Pad1)") (class "Default")
      (node (ref "U1") (pin "1") (pinfunction "1_1") (pintype "bidirectional"))
    )
    (net (code "77") (name "unconnected-(U2-ADC-Pad25)") (class "Default")
      (node (ref "U2") (pin "25") (pinfunction "ADC_25") (pintype "bidirectional"))
    )
    (net (code "78") (name "unconnected-(U2-CTS-Pad7)") (class "Default")
      (node (ref "U2") (pin "7") (pinfunction "CTS_7") (pintype "bidirectional"))
    )
    (net (code "79") (name "unconnected-(U2-DBG_RXD-Pad28)") (class "Default")
      (node (ref "U2") (pin "28") (pinfunction "DBG_RXD_28") (pintype "bidirectional"))
    )
    (net (code "80") (name "unconnected-(U2-DBG_TXD-Pad27)") (class "Default")
      (node (ref "U2") (pin "27") (pinfunction "DBG_TXD_27") (pintype "bidirectional"))
    )
    (net (code "81") (name "unconnected-(U2-DCD-Pad5)") (class "Default")
      (node (ref "U2") (pin "5") (pinfunction "DCD_5") (pintype "bidirectional"))
    )
    (net (code "82") (name "unconnected-(U2-DISP_CLK-Pad11)") (class "Default")
      (node (ref "U2") (pin "11") (pinfunction "DISP_CLK_11") (pintype "bidirectional"))
    )
    (net (code "83") (name "unconnected-(U2-DISP_CS-Pad14)") (class "Default")
      (node (ref "U2") (pin "14") (pinfunction "DISP_CS_14") (pintype "bidirectional"))
    )
    (net (code "84") (name "unconnected-(U2-DISP_DATA-Pad12)") (class "Default")
      (node (ref "U2") (pin "12") (pinfunction "DISP_DATA_12") (pintype "bidirectional"))
    )
    (net (code "85") (name "unconnected-(U2-DISP_D{slash}C-Pad13)") (class "Default")
      (node (ref "U2") (pin "13") (pinfunction "DISP_D/C_13") (pintype "bidirectional"))
    )
    (net (code "86") (name "unconnected-(U2-DTR-Pad3)") (class "Default")
      (node (ref "U2") (pin "3") (pinfunction "DTR_3") (pintype "bidirectional"))
    )
    (net (code "87") (name "unconnected-(U2-GPIO1{slash}KBR4-Pad40)") (class "Default")
      (node (ref "U2") (pin "40") (pinfunction "GPIO1/KBR4_40") (pintype "bidirectional"))
    )
    (net (code "88") (name "unconnected-(U2-GPIO2{slash}KBR3-Pad41)") (class "Default")
      (node (ref "U2") (pin "41") (pinfunction "GPIO2/KBR3_41") (pintype "bidirectional"))
    )
    (net (code "89") (name "unconnected-(U2-GPIO3{slash}KBR2-Pad42)") (class "Default")
      (node (ref "U2") (pin "42") (pinfunction "GPIO3/KBR2_42") (pintype "bidirectional"))
    )
    (net (code "90") (name "unconnected-(U2-GPIO4{slash}KBR1-Pad43)") (class "Default")
      (node (ref "U2") (pin "43") (pinfunction "GPIO4/KBR1_43") (pintype "bidirectional"))
    )
    (net (code "91") (name "unconnected-(U2-GPIO5{slash}KBR0-Pad44)") (class "Default")
      (node (ref "U2") (pin "44") (pinfunction "GPIO5/KBR0_44") (pintype "bidirectional"))
    )
    (net (code "92") (name "unconnected-(U2-GPIO6{slash}KBC4-Pad47)") (class "Default")
      (node (ref "U2") (pin "47") (pinfunction "GPIO6/KBC4_47") (pintype "bidirectional"))
    )
    (net (code "93") (name "unconnected-(U2-GPIO7{slash}KBC3-Pad48)") (class "Default")
      (node (ref "U2") (pin "48") (pinfunction "GPIO7/KBC3_48") (pintype "bidirectional"))
    )
    (net (code "94") (name "unconnected-(U2-GPIO8{slash}KBC2-Pad49)") (class "Default")
      (node (ref "U2") (pin "49") (pinfunction "GPIO8/KBC2_49") (pintype "bidirectional"))
    )
    (net (code "95") (name "unconnected-(U2-GPIO9{slash}KBC1-Pad50)") (class "Default")
      (node (ref "U2") (pin "50") (pinfunction "GPIO9/KBC1_50") (pintype "bidirectional"))
    )
    (net (code "96") (name "unconnected-(U2-GPIO10-Pad51)") (class "Default")
      (node (ref "U2") (pin "51") (pinfunction "GPIO10_51") (pintype "bidirectional"))
    )
    (net (code "97") (name "unconnected-(U2-GPIO11-Pad67)") (class "Default")
      (node (ref "U2") (pin "67") (pinfunction "GPIO11_67") (pintype "bidirectional"))
    )
    (net (code "98") (name "unconnected-(U2-GPIO12-Pad68)") (class "Default")
      (node (ref "U2") (pin "68") (pinfunction "GPIO12_68") (pintype "bidirectional"))
    )
    (net (code "99") (name "unconnected-(U2-LINEIN_L-Pad24)") (class "Default")
      (node (ref "U2") (pin "24") (pinfunction "LINEIN_L_24") (pintype "bidirectional"))
    )
    (net (code "100") (name "unconnected-(U2-LINEIN_R-Pad23)") (class "Default")
      (node (ref "U2") (pin "23") (pinfunction "LINEIN_R_23") (pintype "bidirectional"))
    )
    (net (code "101") (name "unconnected-(U2-NC-Pad2)") (class "Default")
      (node (ref "U2") (pin "2") (pinfunction "NC_2") (pintype "no_connect"))
    )
    (net (code "102") (name "unconnected-(U2-NC-Pad6)") (class "Default")
      (node (ref "U2") (pin "6") (pinfunction "NC_6") (pintype "no_connect"))
    )
    (net (code "103") (name "unconnected-(U2-NRESET-Pad16)") (class "Default")
      (node (ref "U2") (pin "16") (pinfunction "NRESET_16") (pintype "input"))
    )
    (net (code "104") (name "unconnected-(U2-PWM1-Pad35)") (class "Default")
      (node (ref "U2") (pin "35") (pinfunction "PWM1_35") (pintype "bidirectional"))
    )
    (net (code "105") (name "unconnected-(U2-PWM2-Pad36)") (class "Default")
      (node (ref "U2") (pin "36") (pinfunction "PWM2_36") (pintype "bidirectional"))
    )
    (net (code "106") (name "unconnected-(U2-RTS-Pad8)") (class "Default")
      (node (ref "U2") (pin "8") (pinfunction "RTS_8") (pintype "bidirectional"))
    )
    (net (code "107") (name "unconnected-(U2-SCL-Pad38)") (class "Default")
      (node (ref "U2") (pin "38") (pinfunction "SCL_38") (pintype "bidirectional"))
    )
    (net (code "108") (name "unconnected-(U2-SDA-Pad37)") (class "Default")
      (node (ref "U2") (pin "37") (pinfunction "SDA_37") (pintype "bidirectional"))
    )
    (net (code "109") (name "unconnected-(U2-SIM_PRESENCE-Pad34)") (class "Default")
      (node (ref "U2") (pin "34") (pinfunction "SIM_PRESENCE_34") (pintype "bidirectional"))
    )
    (net (code "110") (name "unconnected-(U3-ADC7-Pad22)") (class "Default")
      (node (ref "U3") (pin "22") (pinfunction "ADC7_22") (pintype "bidirectional"))
    )
    (net (code "111") (name "unconnected-(U6-1PPS-Pad6)") (class "Default")
      (node (ref "U6") (pin "6") (pinfunction "1PPS_6") (pintype "output"))
    )
    (net (code "112") (name "unconnected-(U6-NC-Pad2)") (class "Default")
      (node (ref "U6") (pin "2") (pinfunction "NC_2") (pintype "bidirectional"))
    )
    (net (code "113") (name "unconnected-(U6-NC-Pad7)") (class "Default")
      (node (ref "U6") (pin "7") (pinfunction "NC_7") (pintype "bidirectional"))
    )
    (net (code "114") (name "unconnected-(U7-CSB-Pad10)") (class "Default")
      (node (ref "U7") (pin "10") (pinfunction "CSB_10") (pintype "bidirectional"))
    )
    (net (code "115") (name "unconnected-(X1-PadD+)") (class "Default")
      (node (ref "X1") (pin "D+") (pinfunction "D+_D+") (pintype "bidirectional"))
    )
    (net (code "116") (name "unconnected-(X1-PadD-)") (class "Default")
      (node (ref "X1") (pin "D-") (pinfunction "D-_D-") (pintype "bidirectional"))
    )
  )
)
